# Simple_LED_Circuit.net
KiCad netlist of a schematic drawn in EAGLE
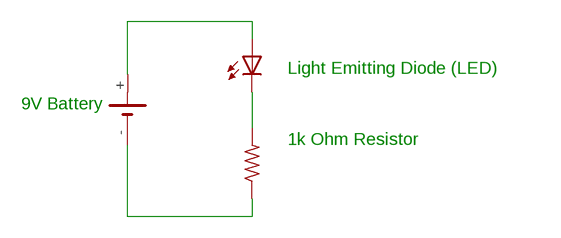
[diagram p0: schematic, sheet 1]

(export (version "E")
  (design (tool "Eeschema 10.0.6"))
  (components
    (comp (ref "9V")
      (value "SL-150-1/2AA/PR")
      (footprint "eagle-import:SL-150-1_2AA_PR")
      (libsource (lib "eagle-import") (part "SL-150-1/2AA/PR"))
    )
    (comp (ref "LED2")
      (value "LAP4-BOTTOM")
      (footprint "eagle-import:P47F-BOTTOM")
      (libsource (lib "eagle-import") (part "P4-BOTTOMLA"))
    )
    (comp (ref "R1")
      (value "R-US_0411/12")
      (footprint "eagle-import:0411_12")
      (libsource (lib "eagle-import") (part "R-US_0411/12"))
    )
  )
  (nets
    (net (code "1") (name "Net-(9V-Pad+)") (class "Default")
      (node (ref "9V") (pin "+") (pinfunction "+_+") (pintype "passive"))
      (node (ref "LED2") (pin "A") (pinfunction "A_A") (pintype "passive"))
    )
    (net (code "2") (name "Net-(9V-Pad-)") (class "Default")
      (node (ref "9V") (pin "-") (pinfunction "-_-") (pintype "passive"))
      (node (ref "R1") (pin "1") (pinfunction "1_1") (pintype "passive"))
    )
    (net (code "3") (name "Net-(LED2-PadC)") (class "Default")
      (node (ref "LED2") (pin "C") (pinfunction "C_C") (pintype "passive"))
      (node (ref "R1") (pin "2") (pinfunction "2_2") (pintype "passive"))
    )
  )
)
